# Opto_Isolator_Breakout.net
KiCad netlist of a schematic drawn in EAGLE
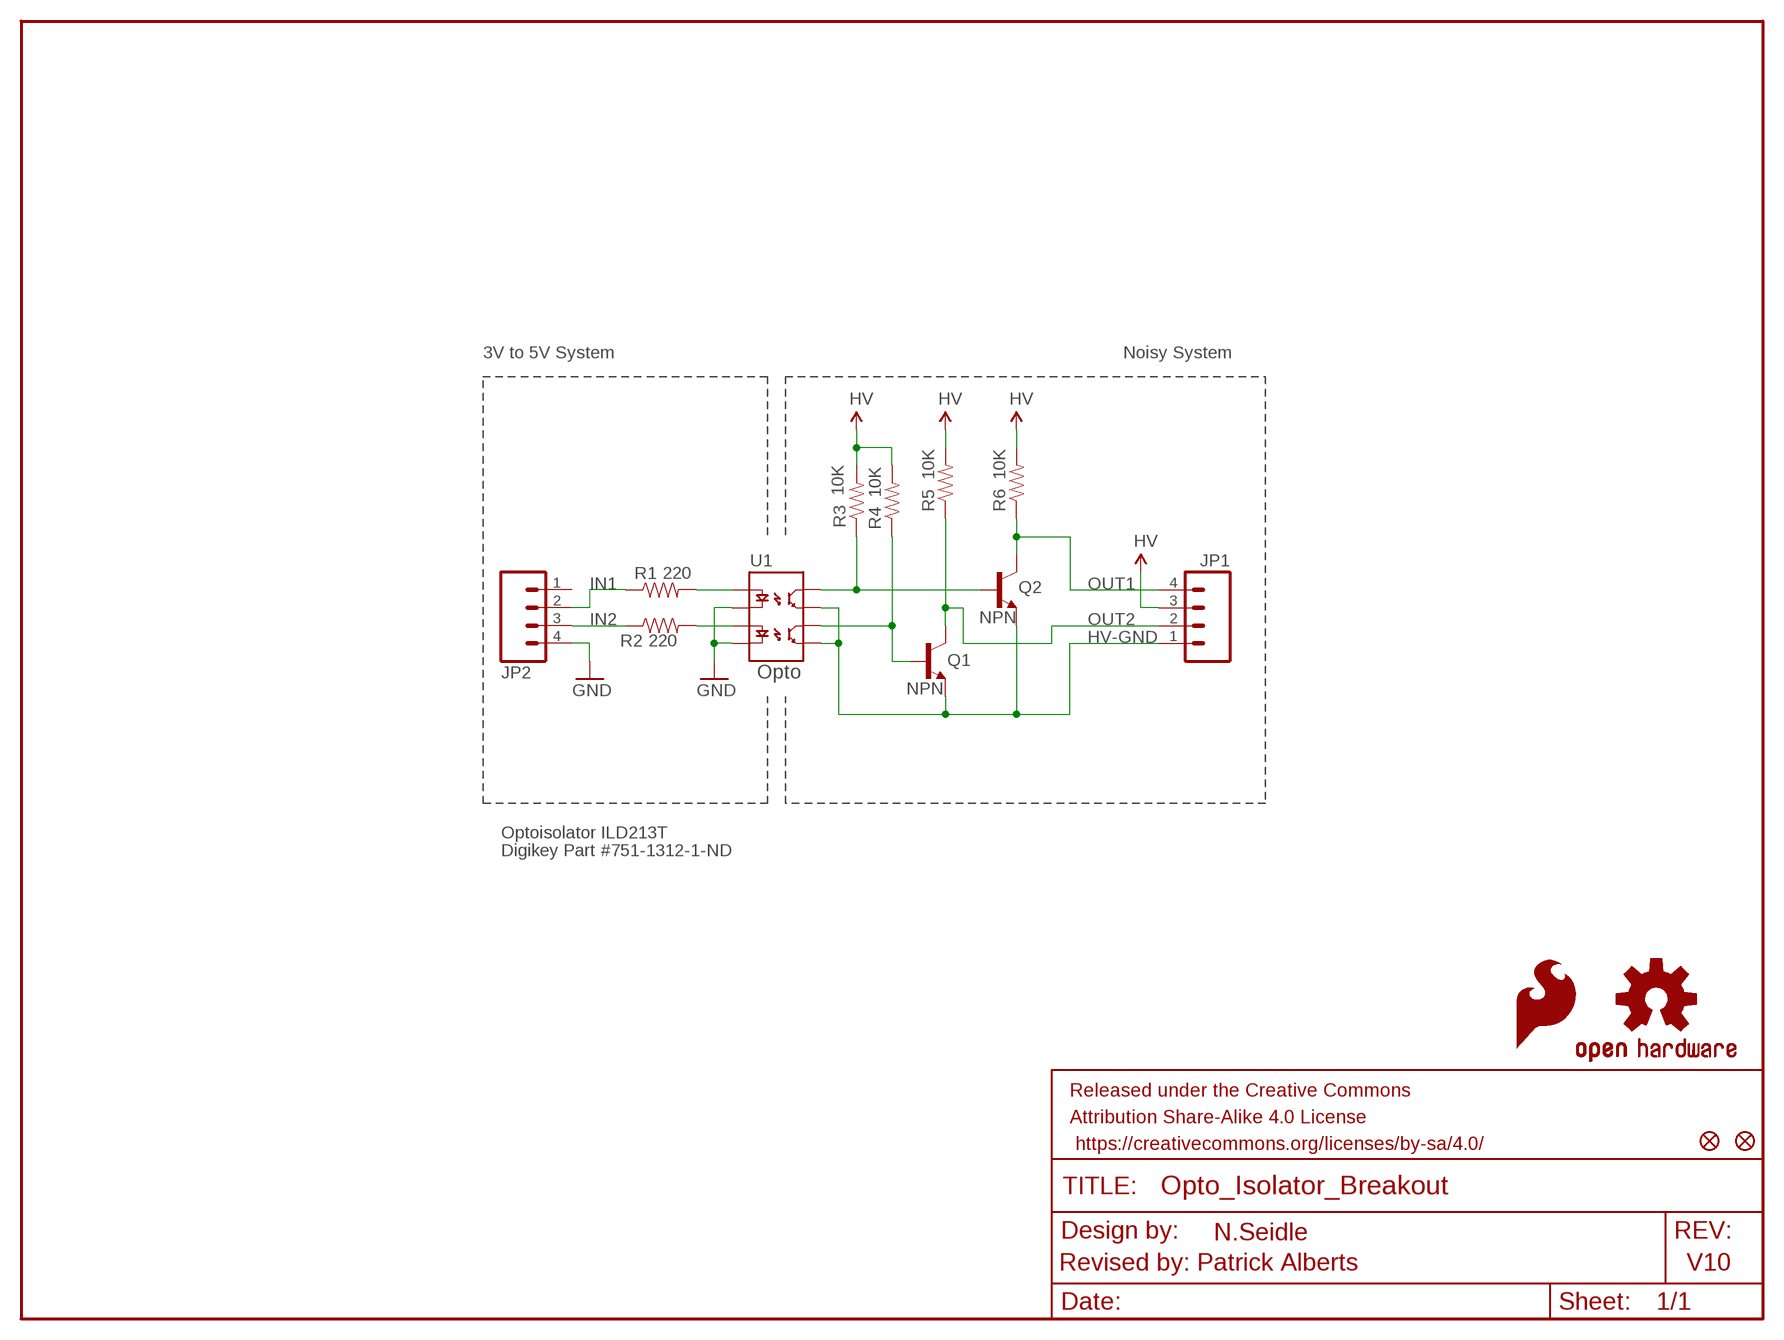
[diagram p0: schematic, sheet 1]

(export (version "E")
  (design (tool "Eeschema 10.0.6"))
  (components
    (comp (ref "FRAME1")
      (value "FRAME-LETTER")
      (footprint "eagle-import:CREATIVE_COMMONS")
      (fields (field (name "DESIGNER") "NAME"))
      (libsource (lib "eagle-import") (part "FRAME-LETTER"))
    )
    (comp (ref "JP1")
      (value "M04PTH")
      (footprint "eagle-import:1X04")
      (libsource (lib "eagle-import") (part "M04PTH"))
    )
    (comp (ref "JP2")
      (value "M04PTH")
      (footprint "eagle-import:1X04")
      (libsource (lib "eagle-import") (part "M04PTH"))
    )
    (comp (ref "LOGO1")
      (value "OSHW-LOGOS")
      (footprint "eagle-import:OSHW-LOGO-S")
      (libsource (lib "eagle-import") (part "OSHW-LOGOS"))
    )
    (comp (ref "LOGO2")
      (value "SFE_LOGO_FLAME.1_INCH")
      (footprint "eagle-import:SFE_LOGO_FLAME_.1")
      (libsource (lib "eagle-import") (part "SFE_LOGO_FLAME.1_INCH"))
    )
    (comp (ref "Q1")
      (value "NPN")
      (footprint "eagle-import:SOT23-3")
      (libsource (lib "eagle-import") (part "TRANSISTOR_NPNMMBT2222A"))
    )
    (comp (ref "Q2")
      (value "NPN")
      (footprint "eagle-import:SOT23-3")
      (libsource (lib "eagle-import") (part "TRANSISTOR_NPNMMBT2222A"))
    )
    (comp (ref "R1")
      (value "220")
      (footprint "eagle-import:0603-RES")
      (libsource (lib "eagle-import") (part "220OHM-1/10W-1%(0603)"))
    )
    (comp (ref "R2")
      (value "220")
      (footprint "eagle-import:0603-RES")
      (libsource (lib "eagle-import") (part "220OHM-1/10W-1%(0603)"))
    )
    (comp (ref "R3")
      (value "10K")
      (footprint "eagle-import:0603-RES")
      (libsource (lib "eagle-import") (part "10KOHM1/10W1%(0603)0603"))
    )
    (comp (ref "R4")
      (value "10K")
      (footprint "eagle-import:0603-RES")
      (libsource (lib "eagle-import") (part "10KOHM1/10W1%(0603)0603"))
    )
    (comp (ref "R5")
      (value "10K")
      (footprint "eagle-import:0603-RES")
      (libsource (lib "eagle-import") (part "10KOHM1/10W1%(0603)0603"))
    )
    (comp (ref "R6")
      (value "10K")
      (footprint "eagle-import:0603-RES")
      (libsource (lib "eagle-import") (part "10KOHM1/10W1%(0603)0603"))
    )
    (comp (ref "U$2")
      (value "FIDUCIALUFIDUCIAL")
      (footprint "eagle-import:MICRO-FIDUCIAL")
      (libsource (lib "eagle-import") (part "FIDUCIALUFIDUCIAL"))
    )
    (comp (ref "U$3")
      (value "FIDUCIALUFIDUCIAL")
      (footprint "eagle-import:MICRO-FIDUCIAL")
      (libsource (lib "eagle-import") (part "FIDUCIALUFIDUCIAL"))
    )
    (comp (ref "U1")
      (value "OPTOISOLATOR-2SOIC8")
      (footprint "eagle-import:SO08-2")
      (libsource (lib "eagle-import") (part "OPTOISOLATOR-2SOIC8"))
    )
  )
  (nets
    (net (code "1") (name "/HV-GND") (class "Default")
      (node (ref "JP1") (pin "1") (pinfunction "1_1") (pintype "passive"))
      (node (ref "Q1") (pin "2") (pinfunction "E_2") (pintype "passive"))
      (node (ref "Q2") (pin "2") (pinfunction "E_2") (pintype "passive"))
      (node (ref "U1") (pin "5") (pinfunction "EM2_5") (pintype "bidirectional"))
      (node (ref "U1") (pin "7") (pinfunction "EM1_7") (pintype "bidirectional"))
    )
    (net (code "2") (name "/IN1") (class "Default")
      (node (ref "JP2") (pin "2") (pinfunction "2_2") (pintype "passive"))
      (node (ref "R1") (pin "1") (pinfunction "1_1") (pintype "passive"))
    )
    (net (code "3") (name "/IN2") (class "Default")
      (node (ref "JP2") (pin "3") (pinfunction "3_3") (pintype "passive"))
      (node (ref "R2") (pin "1") (pinfunction "1_1") (pintype "passive"))
    )
    (net (code "4") (name "/OUT1") (class "Default")
      (node (ref "JP1") (pin "4") (pinfunction "4_4") (pintype "passive"))
      (node (ref "Q2") (pin "3") (pinfunction "C_3") (pintype "passive"))
      (node (ref "R6") (pin "1") (pinfunction "1_1") (pintype "passive"))
    )
    (net (code "5") (name "/OUT2") (class "Default")
      (node (ref "JP1") (pin "2") (pinfunction "2_2") (pintype "passive"))
      (node (ref "Q1") (pin "3") (pinfunction "C_3") (pintype "passive"))
      (node (ref "R5") (pin "1") (pinfunction "1_1") (pintype "passive"))
    )
    (net (code "6") (name "GND") (class "Default")
      (node (ref "JP2") (pin "4") (pinfunction "4_4") (pintype "passive"))
      (node (ref "U1") (pin "2") (pinfunction "C1_2") (pintype "bidirectional"))
      (node (ref "U1") (pin "4") (pinfunction "C2_4") (pintype "bidirectional"))
    )
    (net (code "7") (name "HV") (class "Default")
      (node (ref "JP1") (pin "3") (pinfunction "3_3") (pintype "passive"))
      (node (ref "R3") (pin "2") (pinfunction "2_2") (pintype "passive"))
      (node (ref "R4") (pin "2") (pinfunction "2_2") (pintype "passive"))
      (node (ref "R5") (pin "2") (pinfunction "2_2") (pintype "passive"))
      (node (ref "R6") (pin "2") (pinfunction "2_2") (pintype "passive"))
    )
    (net (code "8") (name "Net-(Q1-B)") (class "Default")
      (node (ref "Q1") (pin "1") (pinfunction "B_1") (pintype "passive"))
      (node (ref "R4") (pin "1") (pinfunction "1_1") (pintype "passive"))
      (node (ref "U1") (pin "6") (pinfunction "CL2_6") (pintype "bidirectional"))
    )
    (net (code "9") (name "Net-(Q2-B)") (class "Default")
      (node (ref "Q2") (pin "1") (pinfunction "B_1") (pintype "passive"))
      (node (ref "R3") (pin "1") (pinfunction "1_1") (pintype "passive"))
      (node (ref "U1") (pin "8") (pinfunction "CL1_8") (pintype "bidirectional"))
    )
    (net (code "10") (name "Net-(U1-A1)") (class "Default")
      (node (ref "R1") (pin "2") (pinfunction "2_2") (pintype "passive"))
      (node (ref "U1") (pin "1") (pinfunction "A1_1") (pintype "bidirectional"))
    )
    (net (code "11") (name "Net-(U1-A2)") (class "Default")
      (node (ref "R2") (pin "2") (pinfunction "2_2") (pintype "passive"))
      (node (ref "U1") (pin "3") (pinfunction "A2_3") (pintype "bidirectional"))
    )
    (net (code "12") (name "unconnected-(JP2-Pad1)") (class "Default")
      (node (ref "JP2") (pin "1") (pinfunction "1_1") (pintype "passive"))
    )
  )
)
